# SCHMIDT.net
KiCad netlist of a schematic drawn in Altium Designer
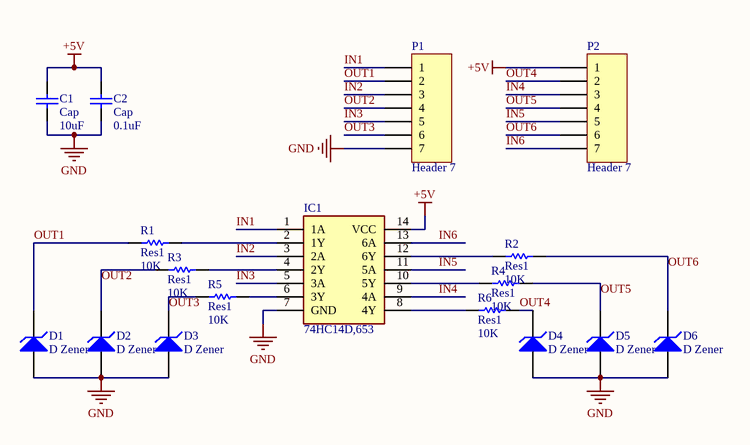
[diagram p0: SCHMIDT.SchDoc]

(export (version "E")
  (design (tool "Eeschema 10.0.6"))
  (components
    (comp (ref "C1")
      (value "Cap")
      (footprint "C1206")
      (description "Capacitor")
      (fields (field (name "ALTIUM_VALUE") "10uF") (field (name "PUBLISHER") "Altium Limited"))
      (libsource (lib "Miscellaneous Devices") (part "Cap"))
    )
    (comp (ref "C2")
      (value "Cap")
      (footprint "1608[0603]")
      (description "Capacitor")
      (fields (field (name "ALTIUM_VALUE") "0.1uF") (field (name "PUBLISHER") "Altium Limited"))
      (libsource (lib "Miscellaneous Devices") (part "Cap"))
    )
    (comp (ref "D1")
      (value "D Zener")
      (footprint "C1206")
      (description "Zener Diode")
      (fields (field (name "PUBLISHER") "Altium Limited"))
      (libsource (lib "Miscellaneous Devices") (part "D Zener"))
    )
    (comp (ref "D2")
      (value "D Zener")
      (footprint "C1206")
      (description "Zener Diode")
      (fields (field (name "PUBLISHER") "Altium Limited"))
      (libsource (lib "Miscellaneous Devices") (part "D Zener"))
    )
    (comp (ref "D3")
      (value "D Zener")
      (footprint "C1206")
      (description "Zener Diode")
      (fields (field (name "PUBLISHER") "Altium Limited"))
      (libsource (lib "Miscellaneous Devices") (part "D Zener"))
    )
    (comp (ref "D4")
      (value "D Zener")
      (footprint "C1206")
      (description "Zener Diode")
      (fields (field (name "PUBLISHER") "Altium Limited"))
      (libsource (lib "Miscellaneous Devices") (part "D Zener"))
    )
    (comp (ref "D5")
      (value "D Zener")
      (footprint "C1206")
      (description "Zener Diode")
      (fields (field (name "PUBLISHER") "Altium Limited"))
      (libsource (lib "Miscellaneous Devices") (part "D Zener"))
    )
    (comp (ref "D6")
      (value "D Zener")
      (footprint "C1206")
      (description "Zener Diode")
      (fields (field (name "PUBLISHER") "Altium Limited"))
      (libsource (lib "Miscellaneous Devices") (part "D Zener"))
    )
    (comp (ref "IC1")
      (value "74HC14D,653")
      (footprint "SamacSys:SOIC127P600X175-14N")
      (description "Integrated Circuit")
      (fields (field (name "MOUSER PART NUMBER") "771-74HC14D-T") (field (name "RS PART NUMBER") "1707953"))
      (libsource (lib "*") (part "74HC14D,653"))
    )
    (comp (ref "P1")
      (value "Header 7")
      (footprint "HDR1X7")
      (description "Header, 7-Pin")
      (fields (field (name "PUBLISHER") "Altium Limited"))
      (libsource (lib "Miscellaneous Connectors") (part "Header 7"))
    )
    (comp (ref "P2")
      (value "Header 7")
      (footprint "HDR1X7")
      (description "Header, 7-Pin")
      (fields (field (name "PUBLISHER") "Altium Limited"))
      (libsource (lib "Miscellaneous Connectors") (part "Header 7"))
    )
    (comp (ref "R1")
      (value "Res1")
      (footprint "J1-0603")
      (description "Resistor")
      (fields (field (name "ALTIUM_VALUE") "10K") (field (name "PUBLISHER") "Altium Limited"))
      (libsource (lib "Miscellaneous Devices") (part "Res1"))
    )
    (comp (ref "R2")
      (value "Res1")
      (footprint "J1-0603")
      (description "Resistor")
      (fields (field (name "ALTIUM_VALUE") "10K") (field (name "PUBLISHER") "Altium Limited"))
      (libsource (lib "Miscellaneous Devices") (part "Res1"))
    )
    (comp (ref "R3")
      (value "Res1")
      (footprint "J1-0603")
      (description "Resistor")
      (fields (field (name "ALTIUM_VALUE") "10K") (field (name "PUBLISHER") "Altium Limited"))
      (libsource (lib "Miscellaneous Devices") (part "Res1"))
    )
    (comp (ref "R4")
      (value "Res1")
      (footprint "J1-0603")
      (description "Resistor")
      (fields (field (name "ALTIUM_VALUE") "10K") (field (name "PUBLISHER") "Altium Limited"))
      (libsource (lib "Miscellaneous Devices") (part "Res1"))
    )
    (comp (ref "R5")
      (value "Res1")
      (footprint "J1-0603")
      (description "Resistor")
      (fields (field (name "ALTIUM_VALUE") "10K") (field (name "PUBLISHER") "Altium Limited"))
      (libsource (lib "Miscellaneous Devices") (part "Res1"))
    )
    (comp (ref "R6")
      (value "Res1")
      (footprint "J1-0603")
      (description "Resistor")
      (fields (field (name "ALTIUM_VALUE") "10K") (field (name "PUBLISHER") "Altium Limited"))
      (libsource (lib "Miscellaneous Devices") (part "Res1"))
    )
  )
  (nets
    (net (code "1") (name "+5V") (class "Default")
      (node (ref "C1") (pin "2") (pinfunction "2_2") (pintype "passive"))
      (node (ref "C2") (pin "2") (pinfunction "2_2") (pintype "passive"))
      (node (ref "IC1") (pin "14") (pinfunction "VCC_14") (pintype "passive"))
      (node (ref "P2") (pin "1") (pinfunction "1_1") (pintype "passive"))
    )
    (net (code "2") (name "/IN1") (class "Default")
      (node (ref "IC1") (pin "1") (pinfunction "1A_1") (pintype "passive"))
      (node (ref "P1") (pin "1") (pinfunction "1_1") (pintype "passive"))
    )
    (net (code "3") (name "/IN2") (class "Default")
      (node (ref "IC1") (pin "3") (pinfunction "2A_3") (pintype "passive"))
      (node (ref "P1") (pin "3") (pinfunction "3_3") (pintype "passive"))
    )
    (net (code "4") (name "/IN3") (class "Default")
      (node (ref "IC1") (pin "5") (pinfunction "3A_5") (pintype "passive"))
      (node (ref "P1") (pin "5") (pinfunction "5_5") (pintype "passive"))
    )
    (net (code "5") (name "/IN4") (class "Default")
      (node (ref "IC1") (pin "9") (pinfunction "4A_9") (pintype "passive"))
      (node (ref "P2") (pin "3") (pinfunction "3_3") (pintype "passive"))
    )
    (net (code "6") (name "/IN5") (class "Default")
      (node (ref "IC1") (pin "11") (pinfunction "5A_11") (pintype "passive"))
      (node (ref "P2") (pin "5") (pinfunction "5_5") (pintype "passive"))
    )
    (net (code "7") (name "/IN6") (class "Default")
      (node (ref "IC1") (pin "13") (pinfunction "6A_13") (pintype "passive"))
      (node (ref "P2") (pin "7") (pinfunction "7_7") (pintype "passive"))
    )
    (net (code "8") (name "/OUT1") (class "Default")
      (node (ref "D1") (pin "2") (pinfunction "K_2") (pintype "passive"))
      (node (ref "P1") (pin "2") (pinfunction "2_2") (pintype "passive"))
      (node (ref "R1") (pin "2") (pinfunction "2_2") (pintype "passive"))
    )
    (net (code "9") (name "/OUT2") (class "Default")
      (node (ref "D2") (pin "2") (pinfunction "K_2") (pintype "passive"))
      (node (ref "P1") (pin "4") (pinfunction "4_4") (pintype "passive"))
      (node (ref "R3") (pin "2") (pinfunction "2_2") (pintype "passive"))
    )
    (net (code "10") (name "/OUT3") (class "Default")
      (node (ref "D3") (pin "2") (pinfunction "K_2") (pintype "passive"))
      (node (ref "P1") (pin "6") (pinfunction "6_6") (pintype "passive"))
      (node (ref "R5") (pin "2") (pinfunction "2_2") (pintype "passive"))
    )
    (net (code "11") (name "/OUT4") (class "Default")
      (node (ref "D4") (pin "2") (pinfunction "K_2") (pintype "passive"))
      (node (ref "P2") (pin "2") (pinfunction "2_2") (pintype "passive"))
      (node (ref "R6") (pin "1") (pinfunction "1_1") (pintype "passive"))
    )
    (net (code "12") (name "/OUT5") (class "Default")
      (node (ref "D5") (pin "2") (pinfunction "K_2") (pintype "passive"))
      (node (ref "P2") (pin "4") (pinfunction "4_4") (pintype "passive"))
      (node (ref "R4") (pin "1") (pinfunction "1_1") (pintype "passive"))
    )
    (net (code "13") (name "/OUT6") (class "Default")
      (node (ref "D6") (pin "2") (pinfunction "K_2") (pintype "passive"))
      (node (ref "P2") (pin "6") (pinfunction "6_6") (pintype "passive"))
      (node (ref "R2") (pin "1") (pinfunction "1_1") (pintype "passive"))
    )
    (net (code "14") (name "GND") (class "Default")
      (node (ref "C1") (pin "1") (pinfunction "1_1") (pintype "passive"))
      (node (ref "C2") (pin "1") (pinfunction "1_1") (pintype "passive"))
      (node (ref "D1") (pin "1") (pinfunction "A_1") (pintype "passive"))
      (node (ref "D2") (pin "1") (pinfunction "A_1") (pintype "passive"))
      (node (ref "D3") (pin "1") (pinfunction "A_1") (pintype "passive"))
      (node (ref "D4") (pin "1") (pinfunction "A_1") (pintype "passive"))
      (node (ref "D5") (pin "1") (pinfunction "A_1") (pintype "passive"))
      (node (ref "D6") (pin "1") (pinfunction "A_1") (pintype "passive"))
      (node (ref "IC1") (pin "7") (pinfunction "GND_7") (pintype "passive"))
      (node (ref "P1") (pin "7") (pinfunction "7_7") (pintype "passive"))
    )
    (net (code "15") (name "Net-(IC1-1Y)") (class "Default")
      (node (ref "IC1") (pin "2") (pinfunction "1Y_2") (pintype "passive"))
      (node (ref "R1") (pin "1") (pinfunction "1_1") (pintype "passive"))
    )
    (net (code "16") (name "Net-(IC1-2Y)") (class "Default")
      (node (ref "IC1") (pin "4") (pinfunction "2Y_4") (pintype "passive"))
      (node (ref "R3") (pin "1") (pinfunction "1_1") (pintype "passive"))
    )
    (net (code "17") (name "Net-(IC1-3Y)") (class "Default")
      (node (ref "IC1") (pin "6") (pinfunction "3Y_6") (pintype "passive"))
      (node (ref "R5") (pin "1") (pinfunction "1_1") (pintype "passive"))
    )
    (net (code "18") (name "Net-(IC1-4Y)") (class "Default")
      (node (ref "IC1") (pin "8") (pinfunction "4Y_8") (pintype "passive"))
      (node (ref "R6") (pin "2") (pinfunction "2_2") (pintype "passive"))
    )
    (net (code "19") (name "Net-(IC1-5Y)") (class "Default")
      (node (ref "IC1") (pin "10") (pinfunction "5Y_10") (pintype "passive"))
      (node (ref "R4") (pin "2") (pinfunction "2_2") (pintype "passive"))
    )
    (net (code "20") (name "Net-(IC1-6Y)") (class "Default")
      (node (ref "IC1") (pin "12") (pinfunction "6Y_12") (pintype "passive"))
      (node (ref "R2") (pin "2") (pinfunction "2_2") (pintype "passive"))
    )
  )
)
